# LF_v5_HM10_Conn.net
KiCad netlist of a schematic drawn in Altium Designer
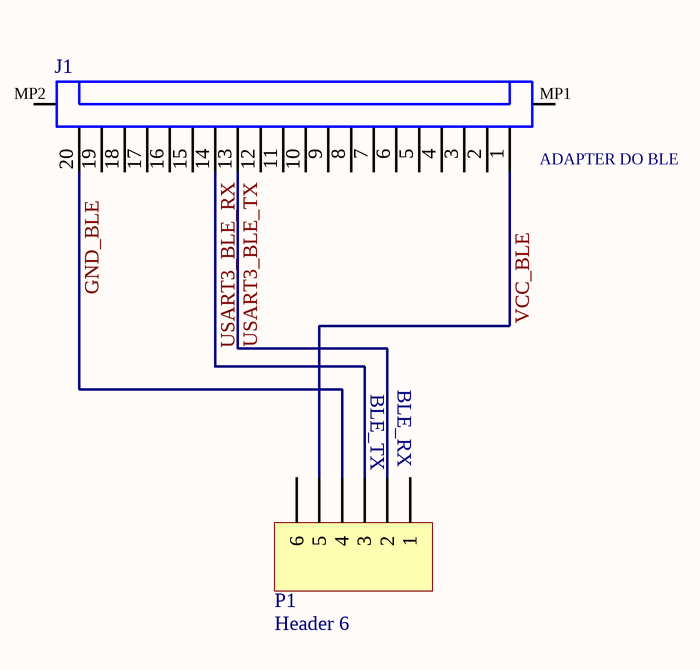
[diagram p0: LF_v5_HM10_Conn.SchDoc]

(export (version "E")
  (design (tool "Eeschema 10.0.6"))
  (components
    (comp (ref "J1")
      (value "ADAPTER DO BLE")
      (footprint "687120183722")
      (description "SMT ZIF Connectors Low Profile WR-FPC, Horizontal, Bottom Contact, pitch 0.5 mm, 20 pins")
      (fields
        (field (name "MANUFACTURER") "Wurth Elektronik")
        (field (name "PART NUMBER") "687120183722")
        (field (name "PUBLISHER") "WurthElektronik")
      )
      (libsource (lib "Altium Content Vault") (part "WE-68X1201XXX22-20"))
    )
    (comp (ref "P1")
      (value "Header 6")
      (footprint "HDR1X6")
      (description "Header, 6-Pin")
      (fields (field (name "PUBLISHER") "Altium Limited"))
      (libsource (lib "Miscellaneous Connectors") (part "Header 6"))
    )
  )
  (nets
    (net (code "1") (name "/GND_BLE") (class "Default")
      (node (ref "J1") (pin "20") (pinfunction "20_20") (pintype "passive"))
      (node (ref "P1") (pin "4") (pinfunction "4_4") (pintype "passive"))
    )
    (net (code "2") (name "/USART3_BLE_RX") (class "Default")
      (node (ref "J1") (pin "14") (pinfunction "14_14") (pintype "passive"))
      (node (ref "P1") (pin "3") (pinfunction "3_3") (pintype "passive"))
    )
    (net (code "3") (name "/USART3_BLE_TX") (class "Default")
      (node (ref "J1") (pin "13") (pinfunction "13_13") (pintype "passive"))
      (node (ref "P1") (pin "2") (pinfunction "2_2") (pintype "passive"))
    )
    (net (code "4") (name "/VCC_BLE") (class "Default")
      (node (ref "J1") (pin "1") (pinfunction "1_1") (pintype "passive"))
      (node (ref "P1") (pin "5") (pinfunction "5_5") (pintype "passive"))
    )
    (net (code "5") (name "unconnected-(J1-Pad2)") (class "Default")
      (node (ref "J1") (pin "2") (pinfunction "2_2") (pintype "passive"))
    )
    (net (code "6") (name "unconnected-(J1-Pad3)") (class "Default")
      (node (ref "J1") (pin "3") (pinfunction "3_3") (pintype "passive"))
    )
    (net (code "7") (name "unconnected-(J1-Pad4)") (class "Default")
      (node (ref "J1") (pin "4") (pinfunction "4_4") (pintype "passive"))
    )
    (net (code "8") (name "unconnected-(J1-Pad5)") (class "Default")
      (node (ref "J1") (pin "5") (pinfunction "5_5") (pintype "passive"))
    )
    (net (code "9") (name "unconnected-(J1-Pad6)") (class "Default")
      (node (ref "J1") (pin "6") (pinfunction "6_6") (pintype "passive"))
    )
    (net (code "10") (name "unconnected-(J1-Pad7)") (class "Default")
      (node (ref "J1") (pin "7") (pinfunction "7_7") (pintype "passive"))
    )
    (net (code "11") (name "unconnected-(J1-Pad8)") (class "Default")
      (node (ref "J1") (pin "8") (pinfunction "8_8") (pintype "passive"))
    )
    (net (code "12") (name "unconnected-(J1-Pad9)") (class "Default")
      (node (ref "J1") (pin "9") (pinfunction "9_9") (pintype "passive"))
    )
    (net (code "13") (name "unconnected-(J1-Pad10)") (class "Default")
      (node (ref "J1") (pin "10") (pinfunction "10_10") (pintype "passive"))
    )
    (net (code "14") (name "unconnected-(J1-Pad11)") (class "Default")
      (node (ref "J1") (pin "11") (pinfunction "11_11") (pintype "passive"))
    )
    (net (code "15") (name "unconnected-(J1-Pad12)") (class "Default")
      (node (ref "J1") (pin "12") (pinfunction "12_12") (pintype "passive"))
    )
    (net (code "16") (name "unconnected-(J1-Pad15)") (class "Default")
      (node (ref "J1") (pin "15") (pinfunction "15_15") (pintype "passive"))
    )
    (net (code "17") (name "unconnected-(J1-Pad16)") (class "Default")
      (node (ref "J1") (pin "16") (pinfunction "16_16") (pintype "passive"))
    )
    (net (code "18") (name "unconnected-(J1-Pad17)") (class "Default")
      (node (ref "J1") (pin "17") (pinfunction "17_17") (pintype "passive"))
    )
    (net (code "19") (name "unconnected-(J1-Pad18)") (class "Default")
      (node (ref "J1") (pin "18") (pinfunction "18_18") (pintype "passive"))
    )
    (net (code "20") (name "unconnected-(J1-Pad19)") (class "Default")
      (node (ref "J1") (pin "19") (pinfunction "19_19") (pintype "passive"))
    )
    (net (code "21") (name "unconnected-(J1-PadMP1)") (class "Default")
      (node (ref "J1") (pin "MP1") (pinfunction "MP1_MP1") (pintype "passive"))
    )
    (net (code "22") (name "unconnected-(J1-PadMP2)") (class "Default")
      (node (ref "J1") (pin "MP2") (pinfunction "MP2_MP2") (pintype "passive"))
    )
    (net (code "23") (name "unconnected-(P1-Pad1)") (class "Default")
      (node (ref "P1") (pin "1") (pinfunction "1_1") (pintype "passive"))
    )
    (net (code "24") (name "unconnected-(P1-Pad6)") (class "Default")
      (node (ref "P1") (pin "6") (pinfunction "6_6") (pintype "passive"))
    )
  )
)
